# Receiver.net
KiCad netlist of a schematic drawn in EAGLE
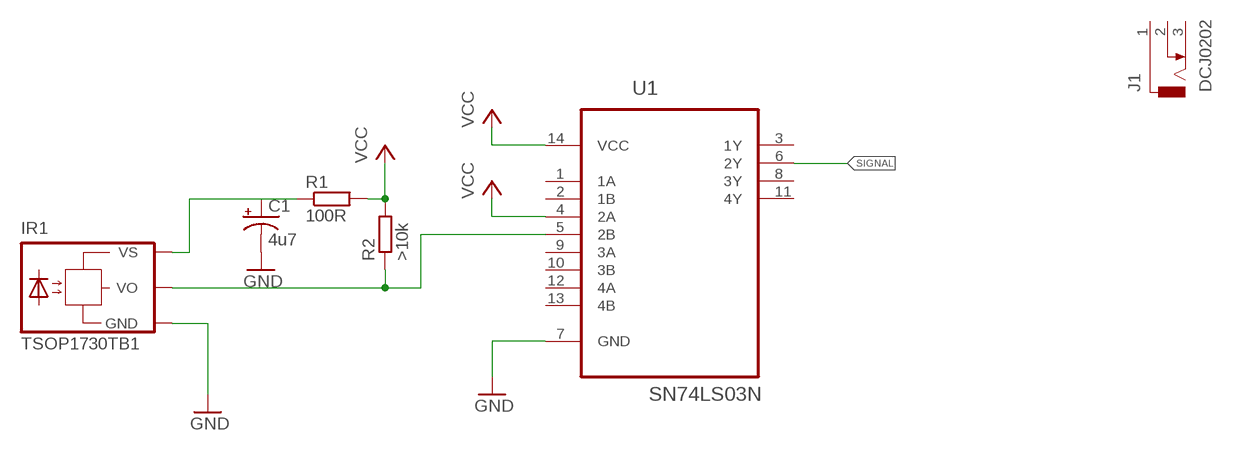
[diagram p0: schematic, sheet 1]

(export (version "E")
  (design (tool "Eeschema 10.0.6"))
  (components
    (comp (ref "C1")
      (value "4u7")
      (footprint "eagle-import:E2-4")
      (libsource (lib "eagle-import") (part "CPOL-USE2-4"))
    )
    (comp (ref "IR1")
      (value "TSOP1730TB1")
      (footprint "eagle-import:TSOP17_TB1")
      (libsource (lib "eagle-import") (part "TSOP17TB130"))
    )
    (comp (ref "J1")
      (value "DCJ0202")
      (footprint "eagle-import:DCJ0202")
      (libsource (lib "eagle-import") (part "DCJ0202"))
    )
    (comp (ref "R1")
      (value "100R")
      (footprint "eagle-import:0204_5")
      (libsource (lib "eagle-import") (part "R-EU_0204/5"))
    )
    (comp (ref "R2")
      (value ">10k")
      (footprint "eagle-import:0204_5")
      (libsource (lib "eagle-import") (part "R-EU_0204/5"))
    )
    (comp (ref "U1")
      (value "SN74LS03N")
      (footprint "eagle-import:DIP254P762X508-14")
      (libsource (lib "eagle-import") (part "SN74LS03N"))
    )
  )
  (nets
    (net (code "1") (name "GND") (class "Default")
      (node (ref "C1") (pin "-") (pinfunction "-_-") (pintype "passive"))
      (node (ref "IR1") (pin "GND") (pinfunction "GND_GND") (pintype "power_in"))
      (node (ref "U1") (pin "7") (pinfunction "GND_7") (pintype "passive"))
    )
    (net (code "2") (name "Net-(C1-Pad+)") (class "Default")
      (node (ref "C1") (pin "+") (pinfunction "+_+") (pintype "passive"))
      (node (ref "IR1") (pin "VS") (pinfunction "VS_VS") (pintype "power_in"))
      (node (ref "R1") (pin "1") (pinfunction "1_1") (pintype "passive"))
    )
    (net (code "3") (name "Net-(U1-2B)") (class "Default")
      (node (ref "IR1") (pin "VO") (pinfunction "VO_VO") (pintype "open_collector"))
      (node (ref "R2") (pin "1") (pinfunction "1_1") (pintype "passive"))
      (node (ref "U1") (pin "5") (pinfunction "2B_5") (pintype "input"))
    )
    (net (code "4") (name "SIGNAL") (class "Default")
      (node (ref "U1") (pin "6") (pinfunction "2Y_6") (pintype "output"))
    )
    (net (code "5") (name "VCC") (class "Default")
      (node (ref "R1") (pin "2") (pinfunction "2_2") (pintype "passive"))
      (node (ref "R2") (pin "2") (pinfunction "2_2") (pintype "passive"))
      (node (ref "U1") (pin "14") (pinfunction "VCC_14") (pintype "input"))
      (node (ref "U1") (pin "4") (pinfunction "2A_4") (pintype "input"))
    )
    (net (code "6") (name "unconnected-(J1-Pad1)") (class "Default")
      (node (ref "J1") (pin "1") (pinfunction "1_1") (pintype "passive"))
    )
    (net (code "7") (name "unconnected-(J1-Pad2)") (class "Default")
      (node (ref "J1") (pin "2") (pinfunction "2_2") (pintype "passive"))
    )
    (net (code "8") (name "unconnected-(J1-Pad3)") (class "Default")
      (node (ref "J1") (pin "3") (pinfunction "3_3") (pintype "passive"))
    )
    (net (code "9") (name "unconnected-(U1-1A-Pad1)") (class "Default")
      (node (ref "U1") (pin "1") (pinfunction "1A_1") (pintype "input"))
    )
    (net (code "10") (name "unconnected-(U1-1B-Pad2)") (class "Default")
      (node (ref "U1") (pin "2") (pinfunction "1B_2") (pintype "input"))
    )
    (net (code "11") (name "unconnected-(U1-1Y-Pad3)") (class "Default")
      (node (ref "U1") (pin "3") (pinfunction "1Y_3") (pintype "output"))
    )
    (net (code "12") (name "unconnected-(U1-3A-Pad9)") (class "Default")
      (node (ref "U1") (pin "9") (pinfunction "3A_9") (pintype "input"))
    )
    (net (code "13") (name "unconnected-(U1-3B-Pad10)") (class "Default")
      (node (ref "U1") (pin "10") (pinfunction "3B_10") (pintype "input"))
    )
    (net (code "14") (name "unconnected-(U1-3Y-Pad8)") (class "Default")
      (node (ref "U1") (pin "8") (pinfunction "3Y_8") (pintype "output"))
    )
    (net (code "15") (name "unconnected-(U1-4A-Pad12)") (class "Default")
      (node (ref "U1") (pin "12") (pinfunction "4A_12") (pintype "input"))
    )
    (net (code "16") (name "unconnected-(U1-4B-Pad13)") (class "Default")
      (node (ref "U1") (pin "13") (pinfunction "4B_13") (pintype "input"))
    )
    (net (code "17") (name "unconnected-(U1-4Y-Pad11)") (class "Default")
      (node (ref "U1") (pin "11") (pinfunction "4Y_11") (pintype "output"))
    )
  )
)
